# Scheme_Indication.net
KiCad netlist of a schematic drawn in Altium Designer
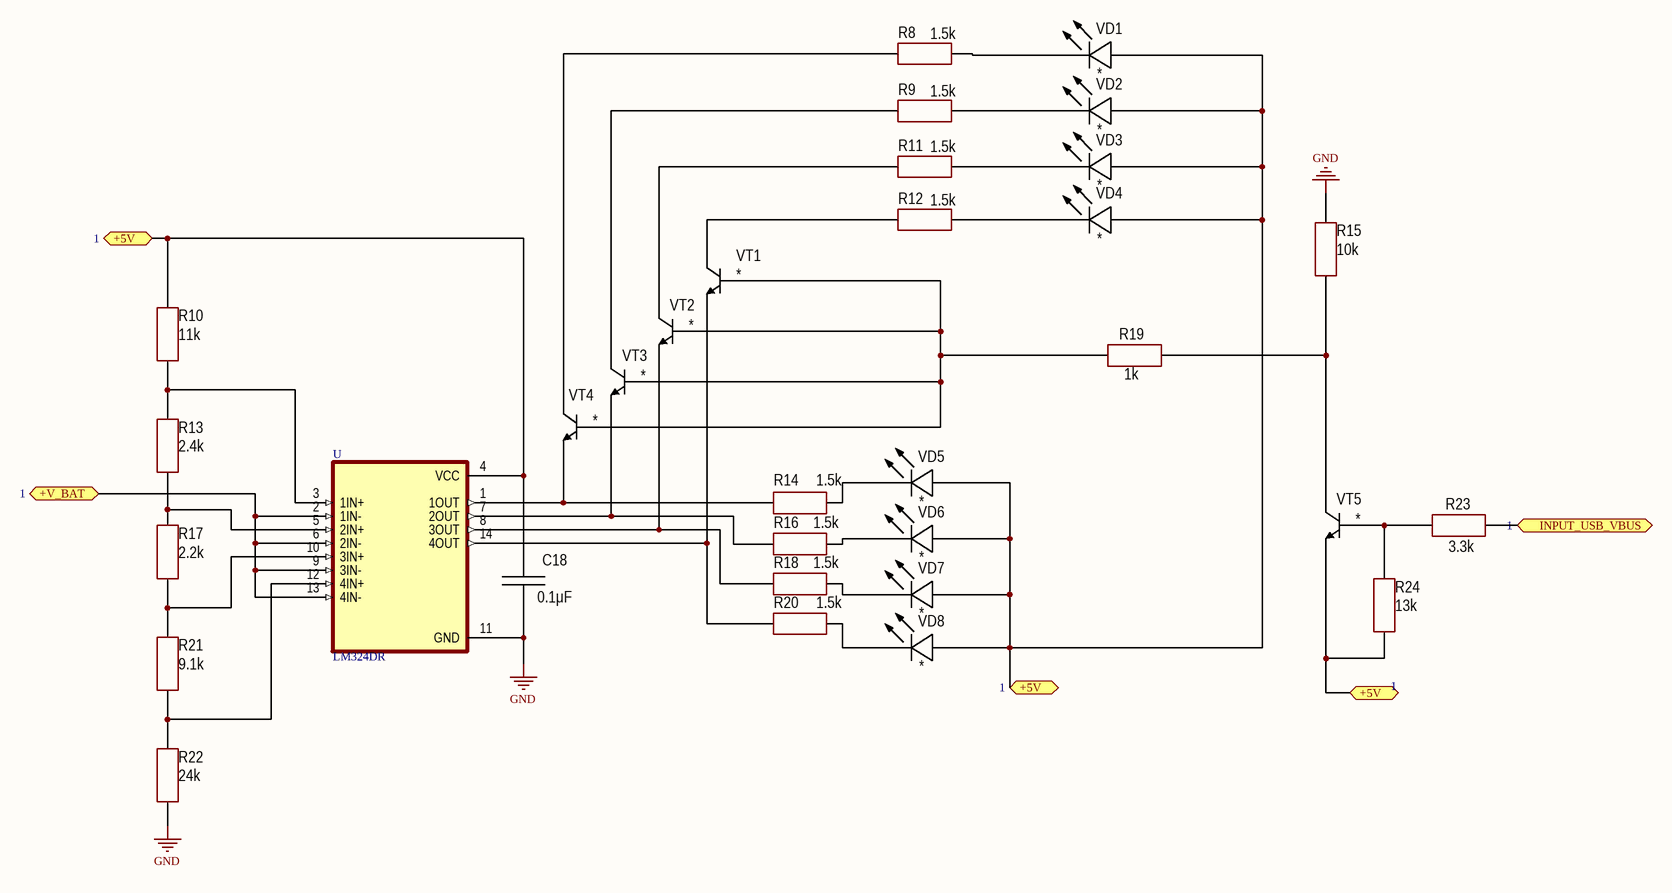
[diagram p0: Scheme_Indication.SchDoc]

(export (version "E")
  (design (tool "Eeschema 10.0.6"))
  (components
    (comp (ref "C18")
      (value "0.1μF")
      (footprint "StandardCase:CAP: 1206")
      (fields
        (field (name "MANUFACTURER") "Yageo")
        (field (name "PARTNUMBER") "CC1206KRX7R9BB104")
        (field (name "VALUEMANUFACTURERPARTNUMBER") "Ceramic capacitor, 0.1μF, X7R, ±10%, 50V, 1206, -55...+125°C")
      )
      (libsource (lib "Capacitor") (part "Ceramic_1206"))
    )
    (comp (ref "R8")
      (value "1.5k")
      (footprint "StandardCase:RES: 1206")
      (fields
        (field (name "MANUFACTURER") "Yageo")
        (field (name "PARTNUMBER") "RC1206JR-07100RL")
        (field (name "VALUEMANUFACTURERPARTNUMBER") "Resistor film, 1.5k, ±5%, 1206, 0.25W, -55...+125°C")
      )
      (libsource (lib "") (part "Resistor_1206_3"))
    )
    (comp (ref "R9")
      (value "1.5k")
      (footprint "StandardCase:RES: 1206")
      (fields
        (field (name "MANUFACTURER") "Yageo")
        (field (name "PARTNUMBER") "RC1206JR-07100RL")
        (field (name "VALUEMANUFACTURERPARTNUMBER") "Resistor film, 1.5k, ±5%, 1206, 0.25W, -55...+125°C")
      )
      (libsource (lib "") (part "Resistor_1206_4"))
    )
    (comp (ref "R10")
      (value "11k")
      (footprint "StandardCase:RES: 1206")
      (fields
        (field (name "MANUFACTURER") "Yageo")
        (field (name "PARTNUMBER") "RC1206JR-07100RL")
        (field (name "VALUEMANUFACTURERPARTNUMBER") "Resistor film, 11k, ±5%, 1206, 0.25W, -55...+125°C")
      )
      (libsource (lib "") (part "Resistor_1206_1"))
    )
    (comp (ref "R11")
      (value "1.5k")
      (footprint "StandardCase:RES: 1206")
      (fields
        (field (name "MANUFACTURER") "Yageo")
        (field (name "PARTNUMBER") "RC1206JR-07100RL")
        (field (name "VALUEMANUFACTURERPARTNUMBER") "Resistor film, 1.5k, ±5%, 1206, 0.25W, -55...+125°C")
      )
      (libsource (lib "Resistor") (part "Resistor_1206"))
    )
    (comp (ref "R12")
      (value "1.5k")
      (footprint "StandardCase:RES: 1206")
      (fields
        (field (name "MANUFACTURER") "Yageo")
        (field (name "PARTNUMBER") "RC1206JR-07100RL")
        (field (name "VALUEMANUFACTURERPARTNUMBER") "Resistor film, 1.5k, ±5%, 1206, 0.25W, -55...+125°C")
      )
      (libsource (lib "") (part "Resistor_1206_4"))
    )
    (comp (ref "R13")
      (value "2.4k")
      (footprint "StandardCase:RES: 1206")
      (fields
        (field (name "MANUFACTURER") "Yageo")
        (field (name "PARTNUMBER") "RC1206JR-07100RL")
        (field (name "VALUEMANUFACTURERPARTNUMBER") "Resistor film, 2.4k, ±5%, 1206, 0.25W, -55...+125°C")
      )
      (libsource (lib "") (part "Resistor_1206_1"))
    )
    (comp (ref "R14")
      (value "1.5k")
      (footprint "StandardCase:RES: 1206")
      (fields
        (field (name "MANUFACTURER") "Yageo")
        (field (name "PARTNUMBER") "RC1206JR-07100RL")
        (field (name "VALUEMANUFACTURERPARTNUMBER") "Resistor film, 1.5k, ±5%, 1206, 0.25W, -55...+125°C")
      )
      (libsource (lib "Resistor") (part "Resistor_1206"))
    )
    (comp (ref "R15")
      (value "10k")
      (footprint "StandardCase:RES: 1206")
      (fields
        (field (name "MANUFACTURER") "Yageo")
        (field (name "PARTNUMBER") "RC1206JR-07100RL")
        (field (name "VALUEMANUFACTURERPARTNUMBER") "Resistor film, 10k, ±5%, 1206, 0.25W, -55...+125°C")
      )
      (libsource (lib "") (part "Resistor_1206_2"))
    )
    (comp (ref "R16")
      (value "1.5k")
      (footprint "StandardCase:RES: 1206")
      (fields
        (field (name "MANUFACTURER") "Yageo")
        (field (name "PARTNUMBER") "RC1206JR-07100RL")
        (field (name "VALUEMANUFACTURERPARTNUMBER") "Resistor film, 1.5k, ±5%, 1206, 0.25W, -55...+125°C")
      )
      (libsource (lib "Resistor") (part "Resistor_1206"))
    )
    (comp (ref "R17")
      (value "2.2k")
      (footprint "StandardCase:RES: 1206")
      (fields
        (field (name "MANUFACTURER") "Yageo")
        (field (name "PARTNUMBER") "RC1206JR-07100RL")
        (field (name "VALUEMANUFACTURERPARTNUMBER") "Resistor film, 2.2k, ±5%, 1206, 0.25W, -55...+125°C")
      )
      (libsource (lib "") (part "Resistor_1206_1"))
    )
    (comp (ref "R18")
      (value "1.5k")
      (footprint "StandardCase:RES: 1206")
      (fields
        (field (name "MANUFACTURER") "Yageo")
        (field (name "PARTNUMBER") "RC1206JR-07100RL")
        (field (name "VALUEMANUFACTURERPARTNUMBER") "Resistor film, 1.5k, ±5%, 1206, 0.25W, -55...+125°C")
      )
      (libsource (lib "Resistor") (part "Resistor_1206"))
    )
    (comp (ref "R19")
      (value "1k")
      (footprint "StandardCase:RES: 1206")
      (fields
        (field (name "MANUFACTURER") "Yageo")
        (field (name "PARTNUMBER") "RC1206JR-07100RL")
        (field (name "VALUEMANUFACTURERPARTNUMBER") "Resistor film, 1k, ±5%, 1206, 0.25W, -55...+125°C")
      )
      (libsource (lib "Resistor") (part "Resistor_1206"))
    )
    (comp (ref "R20")
      (value "1.5k")
      (footprint "StandardCase:RES: 1206")
      (fields
        (field (name "MANUFACTURER") "Yageo")
        (field (name "PARTNUMBER") "RC1206JR-07100RL")
        (field (name "VALUEMANUFACTURERPARTNUMBER") "Resistor film, 1.5k, ±5%, 1206, 0.25W, -55...+125°C")
      )
      (libsource (lib "Resistor") (part "Resistor_1206"))
    )
    (comp (ref "R21")
      (value "9.1k")
      (footprint "StandardCase:RES: 1206")
      (fields
        (field (name "MANUFACTURER") "Yageo")
        (field (name "PARTNUMBER") "RC1206JR-07100RL")
        (field (name "VALUEMANUFACTURERPARTNUMBER") "Resistor film, 9.1k, ±5%, 1206, 0.25W, -55...+125°C")
      )
      (libsource (lib "") (part "Resistor_1206_1"))
    )
    (comp (ref "R22")
      (value "24k")
      (footprint "StandardCase:RES: 1206")
      (fields
        (field (name "MANUFACTURER") "Yageo")
        (field (name "PARTNUMBER") "RC1206JR-07100RL")
        (field (name "VALUEMANUFACTURERPARTNUMBER") "Resistor film, 24k, ±5%, 1206, 0.25W, -55...+125°C")
      )
      (libsource (lib "") (part "Resistor_1206_1"))
    )
    (comp (ref "R23")
      (value "3.3k")
      (footprint "StandardCase:RES: 1206")
      (fields
        (field (name "MANUFACTURER") "Yageo")
        (field (name "PARTNUMBER") "RC1206JR-07100RL")
        (field (name "VALUEMANUFACTURERPARTNUMBER") "Resistor film, 3.3k, ±5%, 1206, 0.25W, -55...+125°C")
      )
      (libsource (lib "Resistor") (part "Resistor_1206"))
    )
    (comp (ref "R24")
      (value "13k")
      (footprint "StandardCase:RES: 1206")
      (fields
        (field (name "MANUFACTURER") "Yageo")
        (field (name "PARTNUMBER") "RC1206JR-07100RL")
        (field (name "VALUEMANUFACTURERPARTNUMBER") "Resistor film, 13k, ±5%, 1206, 0.25W, -55...+125°C")
      )
      (libsource (lib "") (part "Resistor_1206_2"))
    )
    (comp (ref "U")
      (value "LM324DR")
      (footprint "SOIC127P600X175-14N")
      (description "4-Channel industry standard operational amplifier 14-SOIC 0 to 70")
      (fields (field (name "MF") "Texas Instruments"))
      (libsource (lib "LM324DR") (part "LM324DR"))
    )
    (comp (ref "VD1") (value "*") (footprint "standard:CH1206LY") (libsource (lib "Discrete") (part "LED")))
    (comp (ref "VD2") (value "*") (footprint "standard:CH1206LY") (libsource (lib "Discrete") (part "LED")))
    (comp (ref "VD3") (value "*") (footprint "standard:CH1206LY") (libsource (lib "Discrete") (part "LED")))
    (comp (ref "VD4") (value "*") (footprint "standard:CH1206LY") (libsource (lib "Discrete") (part "LED")))
    (comp (ref "VD5") (value "*") (footprint "standard:CH1206LY") (libsource (lib "") (part "LED_1")))
    (comp (ref "VD6") (value "*") (footprint "standard:CH1206LY") (libsource (lib "") (part "LED_1")))
    (comp (ref "VD7") (value "*") (footprint "standard:CH1206LY") (libsource (lib "") (part "LED_1")))
    (comp (ref "VD8") (value "*") (footprint "standard:CH1206LY") (libsource (lib "") (part "LED_1")))
    (comp (ref "VT1")
      (value "*")
      (footprint "standard:SOT23_123")
      (description "Bipolar")
      (libsource (lib "Transistor") (part "NPN"))
    )
    (comp (ref "VT2")
      (value "*")
      (footprint "standard:SOT23_123")
      (description "Bipolar")
      (libsource (lib "Transistor") (part "NPN"))
    )
    (comp (ref "VT3")
      (value "*")
      (footprint "standard:SOT23_123")
      (description "Bipolar")
      (libsource (lib "Transistor") (part "NPN"))
    )
    (comp (ref "VT4")
      (value "*")
      (footprint "standard:SOT23_123")
      (description "Bipolar")
      (libsource (lib "Transistor") (part "NPN"))
    )
    (comp (ref "VT5")
      (value "*")
      (footprint "standard:SOT23_123")
      (description "Bipolar")
      (libsource (lib "Transistor") (part "NPN"))
    )
  )
  (nets
    (net (code "1") (name "/+5V") (class "Default")
      (node (ref "C18") (pin "2") (pinfunction "2_2") (pintype "power_in"))
      (node (ref "R10") (pin "2") (pinfunction "2_2") (pintype "passive"))
      (node (ref "R24") (pin "2") (pinfunction "2_2") (pintype "passive"))
      (node (ref "U") (pin "4") (pinfunction "VCC_4") (pintype "power_in"))
      (node (ref "VD1") (pin "1") (pinfunction "A_1") (pintype "passive"))
      (node (ref "VD2") (pin "1") (pinfunction "A_1") (pintype "passive"))
      (node (ref "VD3") (pin "1") (pinfunction "A_1") (pintype "passive"))
      (node (ref "VD4") (pin "1") (pinfunction "A_1") (pintype "passive"))
      (node (ref "VD5") (pin "1") (pinfunction "A_1") (pintype "passive"))
      (node (ref "VD6") (pin "1") (pinfunction "A_1") (pintype "passive"))
      (node (ref "VD7") (pin "1") (pinfunction "A_1") (pintype "passive"))
      (node (ref "VD8") (pin "1") (pinfunction "A_1") (pintype "passive"))
      (node (ref "VT5") (pin "3") (pinfunction "E_3") (pintype "passive"))
    )
    (net (code "2") (name "/+V_BAT") (class "Default")
      (node (ref "U") (pin "13") (pinfunction "4IN-_13") (pintype "input"))
      (node (ref "U") (pin "2") (pinfunction "1IN-_2") (pintype "input"))
      (node (ref "U") (pin "6") (pinfunction "2IN-_6") (pintype "input"))
      (node (ref "U") (pin "9") (pinfunction "3IN-_9") (pintype "input"))
    )
    (net (code "3") (name "/INPUT_USB_VBUS") (class "Default")
      (node (ref "R23") (pin "2") (pinfunction "2_2") (pintype "passive"))
    )
    (net (code "4") (name "GND") (class "Default")
      (node (ref "C18") (pin "1") (pinfunction "1_1") (pintype "power_in"))
      (node (ref "R15") (pin "1") (pinfunction "1_1") (pintype "passive"))
      (node (ref "R22") (pin "1") (pinfunction "1_1") (pintype "passive"))
      (node (ref "U") (pin "11") (pinfunction "GND_11") (pintype "power_in"))
    )
    (net (code "5") (name "Net-(U-1IN+)") (class "Default")
      (node (ref "R10") (pin "1") (pinfunction "1_1") (pintype "passive"))
      (node (ref "R13") (pin "2") (pinfunction "2_2") (pintype "passive"))
      (node (ref "U") (pin "3") (pinfunction "1IN+_3") (pintype "input"))
    )
    (net (code "6") (name "Net-(U-1OUT)") (class "Default")
      (node (ref "R14") (pin "1") (pinfunction "1_1") (pintype "passive"))
      (node (ref "U") (pin "1") (pinfunction "1OUT_1") (pintype "output"))
      (node (ref "VT4") (pin "3") (pinfunction "E_3") (pintype "passive"))
    )
    (net (code "7") (name "Net-(U-2IN+)") (class "Default")
      (node (ref "R13") (pin "1") (pinfunction "1_1") (pintype "passive"))
      (node (ref "R17") (pin "2") (pinfunction "2_2") (pintype "passive"))
      (node (ref "U") (pin "5") (pinfunction "2IN+_5") (pintype "input"))
    )
    (net (code "8") (name "Net-(U-2OUT)") (class "Default")
      (node (ref "R16") (pin "1") (pinfunction "1_1") (pintype "passive"))
      (node (ref "U") (pin "7") (pinfunction "2OUT_7") (pintype "output"))
      (node (ref "VT3") (pin "3") (pinfunction "E_3") (pintype "passive"))
    )
    (net (code "9") (name "Net-(U-3IN+)") (class "Default")
      (node (ref "R17") (pin "1") (pinfunction "1_1") (pintype "passive"))
      (node (ref "R21") (pin "2") (pinfunction "2_2") (pintype "passive"))
      (node (ref "U") (pin "10") (pinfunction "3IN+_10") (pintype "input"))
    )
    (net (code "10") (name "Net-(U-3OUT)") (class "Default")
      (node (ref "R18") (pin "1") (pinfunction "1_1") (pintype "passive"))
      (node (ref "U") (pin "8") (pinfunction "3OUT_8") (pintype "output"))
      (node (ref "VT2") (pin "3") (pinfunction "E_3") (pintype "passive"))
    )
    (net (code "11") (name "Net-(U-4IN+)") (class "Default")
      (node (ref "R21") (pin "1") (pinfunction "1_1") (pintype "passive"))
      (node (ref "R22") (pin "2") (pinfunction "2_2") (pintype "passive"))
      (node (ref "U") (pin "12") (pinfunction "4IN+_12") (pintype "input"))
    )
    (net (code "12") (name "Net-(U-4OUT)") (class "Default")
      (node (ref "R20") (pin "1") (pinfunction "1_1") (pintype "passive"))
      (node (ref "U") (pin "14") (pinfunction "4OUT_14") (pintype "output"))
      (node (ref "VT1") (pin "3") (pinfunction "E_3") (pintype "passive"))
    )
    (net (code "13") (name "Net-(VD1-C)") (class "Default")
      (node (ref "R8") (pin "2") (pinfunction "2_2") (pintype "passive"))
      (node (ref "VD1") (pin "2") (pinfunction "C_2") (pintype "passive"))
    )
    (net (code "14") (name "Net-(VD2-C)") (class "Default")
      (node (ref "R9") (pin "2") (pinfunction "2_2") (pintype "passive"))
      (node (ref "VD2") (pin "2") (pinfunction "C_2") (pintype "passive"))
    )
    (net (code "15") (name "Net-(VD3-C)") (class "Default")
      (node (ref "R11") (pin "2") (pinfunction "2_2") (pintype "passive"))
      (node (ref "VD3") (pin "2") (pinfunction "C_2") (pintype "passive"))
    )
    (net (code "16") (name "Net-(VD4-C)") (class "Default")
      (node (ref "R12") (pin "2") (pinfunction "2_2") (pintype "passive"))
      (node (ref "VD4") (pin "2") (pinfunction "C_2") (pintype "passive"))
    )
    (net (code "17") (name "Net-(VD5-C)") (class "Default")
      (node (ref "R14") (pin "2") (pinfunction "2_2") (pintype "passive"))
      (node (ref "VD5") (pin "2") (pinfunction "C_2") (pintype "passive"))
    )
    (net (code "18") (name "Net-(VD6-C)") (class "Default")
      (node (ref "R16") (pin "2") (pinfunction "2_2") (pintype "passive"))
      (node (ref "VD6") (pin "2") (pinfunction "C_2") (pintype "passive"))
    )
    (net (code "19") (name "Net-(VD7-C)") (class "Default")
      (node (ref "R18") (pin "2") (pinfunction "2_2") (pintype "passive"))
      (node (ref "VD7") (pin "2") (pinfunction "C_2") (pintype "passive"))
    )
    (net (code "20") (name "Net-(VD8-C)") (class "Default")
      (node (ref "R20") (pin "2") (pinfunction "2_2") (pintype "passive"))
      (node (ref "VD8") (pin "2") (pinfunction "C_2") (pintype "passive"))
    )
    (net (code "21") (name "Net-(VT1-B)") (class "Default")
      (node (ref "R19") (pin "1") (pinfunction "1_1") (pintype "passive"))
      (node (ref "VT1") (pin "1") (pinfunction "B_1") (pintype "passive"))
      (node (ref "VT2") (pin "1") (pinfunction "B_1") (pintype "passive"))
      (node (ref "VT3") (pin "1") (pinfunction "B_1") (pintype "passive"))
      (node (ref "VT4") (pin "1") (pinfunction "B_1") (pintype "passive"))
    )
    (net (code "22") (name "Net-(VT1-C)") (class "Default")
      (node (ref "R12") (pin "1") (pinfunction "1_1") (pintype "passive"))
      (node (ref "VT1") (pin "2") (pinfunction "C_2") (pintype "passive"))
    )
    (net (code "23") (name "Net-(VT2-C)") (class "Default")
      (node (ref "R11") (pin "1") (pinfunction "1_1") (pintype "passive"))
      (node (ref "VT2") (pin "2") (pinfunction "C_2") (pintype "passive"))
    )
    (net (code "24") (name "Net-(VT3-C)") (class "Default")
      (node (ref "R9") (pin "1") (pinfunction "1_1") (pintype "passive"))
      (node (ref "VT3") (pin "2") (pinfunction "C_2") (pintype "passive"))
    )
    (net (code "25") (name "Net-(VT4-C)") (class "Default")
      (node (ref "R8") (pin "1") (pinfunction "1_1") (pintype "passive"))
      (node (ref "VT4") (pin "2") (pinfunction "C_2") (pintype "passive"))
    )
    (net (code "26") (name "Net-(VT5-B)") (class "Default")
      (node (ref "R23") (pin "1") (pinfunction "1_1") (pintype "passive"))
      (node (ref "R24") (pin "1") (pinfunction "1_1") (pintype "passive"))
      (node (ref "VT5") (pin "1") (pinfunction "B_1") (pintype "passive"))
    )
    (net (code "27") (name "Net-(VT5-C)") (class "Default")
      (node (ref "R15") (pin "2") (pinfunction "2_2") (pintype "passive"))
      (node (ref "R19") (pin "2") (pinfunction "2_2") (pintype "passive"))
      (node (ref "VT5") (pin "2") (pinfunction "C_2") (pintype "passive"))
    )
  )
)
